# khaliddalkhaldi.net
KiCad netlist of a schematic drawn in EAGLE
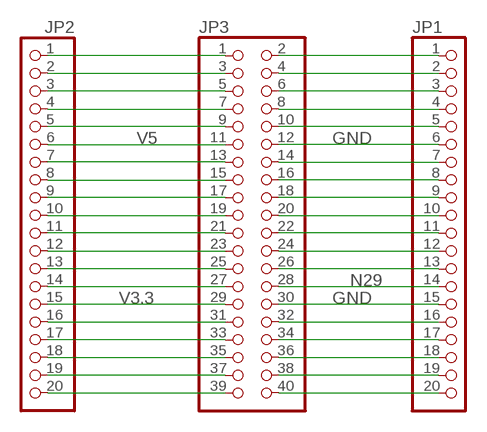
[diagram p0: schematic, sheet 1]

(export (version "E")
  (design (tool "Eeschema 10.0.6"))
  (components
    (comp (ref "JP1")
      (value "PINHD-1X20")
      (footprint "eagle-import:1X20")
      (libsource (lib "eagle-import") (part "PINHD-1X20"))
    )
    (comp (ref "JP2")
      (value "PINHD-1X20")
      (footprint "eagle-import:1X20")
      (libsource (lib "eagle-import") (part "PINHD-1X20"))
    )
    (comp (ref "JP3")
      (value "PINHD-2X20")
      (footprint "eagle-import:2X20")
      (libsource (lib "eagle-import") (part "PINHD-2X20"))
    )
  )
  (nets
    (net (code "1") (name "/GND") (class "Default")
      (node (ref "JP1") (pin "15") (pinfunction "15_15") (pintype "passive"))
      (node (ref "JP1") (pin "6") (pinfunction "6_6") (pintype "passive"))
      (node (ref "JP3") (pin "12") (pinfunction "12_12") (pintype "passive"))
      (node (ref "JP3") (pin "30") (pinfunction "30_30") (pintype "passive"))
    )
    (net (code "2") (name "/N29") (class "Default")
      (node (ref "JP1") (pin "14") (pinfunction "14_14") (pintype "passive"))
      (node (ref "JP3") (pin "28") (pinfunction "28_28") (pintype "passive"))
    )
    (net (code "3") (name "/V3.3") (class "Default")
      (node (ref "JP2") (pin "15") (pinfunction "15_15") (pintype "passive"))
      (node (ref "JP3") (pin "29") (pinfunction "29_29") (pintype "passive"))
    )
    (net (code "4") (name "/V5") (class "Default")
      (node (ref "JP2") (pin "6") (pinfunction "6_6") (pintype "passive"))
      (node (ref "JP3") (pin "11") (pinfunction "11_11") (pintype "passive"))
    )
    (net (code "5") (name "Net-(JP1-Pad1)") (class "Default")
      (node (ref "JP1") (pin "1") (pinfunction "1_1") (pintype "passive"))
      (node (ref "JP3") (pin "2") (pinfunction "2_2") (pintype "passive"))
    )
    (net (code "6") (name "Net-(JP1-Pad2)") (class "Default")
      (node (ref "JP1") (pin "2") (pinfunction "2_2") (pintype "passive"))
      (node (ref "JP3") (pin "4") (pinfunction "4_4") (pintype "passive"))
    )
    (net (code "7") (name "Net-(JP1-Pad3)") (class "Default")
      (node (ref "JP1") (pin "3") (pinfunction "3_3") (pintype "passive"))
      (node (ref "JP3") (pin "6") (pinfunction "6_6") (pintype "passive"))
    )
    (net (code "8") (name "Net-(JP1-Pad4)") (class "Default")
      (node (ref "JP1") (pin "4") (pinfunction "4_4") (pintype "passive"))
      (node (ref "JP3") (pin "8") (pinfunction "8_8") (pintype "passive"))
    )
    (net (code "9") (name "Net-(JP1-Pad5)") (class "Default")
      (node (ref "JP1") (pin "5") (pinfunction "5_5") (pintype "passive"))
      (node (ref "JP3") (pin "10") (pinfunction "10_10") (pintype "passive"))
    )
    (net (code "10") (name "Net-(JP1-Pad7)") (class "Default")
      (node (ref "JP1") (pin "7") (pinfunction "7_7") (pintype "passive"))
      (node (ref "JP3") (pin "14") (pinfunction "14_14") (pintype "passive"))
    )
    (net (code "11") (name "Net-(JP1-Pad8)") (class "Default")
      (node (ref "JP1") (pin "8") (pinfunction "8_8") (pintype "passive"))
      (node (ref "JP3") (pin "16") (pinfunction "16_16") (pintype "passive"))
    )
    (net (code "12") (name "Net-(JP1-Pad9)") (class "Default")
      (node (ref "JP1") (pin "9") (pinfunction "9_9") (pintype "passive"))
      (node (ref "JP3") (pin "18") (pinfunction "18_18") (pintype "passive"))
    )
    (net (code "13") (name "Net-(JP1-Pad10)") (class "Default")
      (node (ref "JP1") (pin "10") (pinfunction "10_10") (pintype "passive"))
      (node (ref "JP3") (pin "20") (pinfunction "20_20") (pintype "passive"))
    )
    (net (code "14") (name "Net-(JP1-Pad11)") (class "Default")
      (node (ref "JP1") (pin "11") (pinfunction "11_11") (pintype "passive"))
      (node (ref "JP3") (pin "22") (pinfunction "22_22") (pintype "passive"))
    )
    (net (code "15") (name "Net-(JP1-Pad12)") (class "Default")
      (node (ref "JP1") (pin "12") (pinfunction "12_12") (pintype "passive"))
      (node (ref "JP3") (pin "24") (pinfunction "24_24") (pintype "passive"))
    )
    (net (code "16") (name "Net-(JP1-Pad13)") (class "Default")
      (node (ref "JP1") (pin "13") (pinfunction "13_13") (pintype "passive"))
      (node (ref "JP3") (pin "26") (pinfunction "26_26") (pintype "passive"))
    )
    (net (code "17") (name "Net-(JP1-Pad16)") (class "Default")
      (node (ref "JP1") (pin "16") (pinfunction "16_16") (pintype "passive"))
      (node (ref "JP3") (pin "32") (pinfunction "32_32") (pintype "passive"))
    )
    (net (code "18") (name "Net-(JP1-Pad17)") (class "Default")
      (node (ref "JP1") (pin "17") (pinfunction "17_17") (pintype "passive"))
      (node (ref "JP3") (pin "34") (pinfunction "34_34") (pintype "passive"))
    )
    (net (code "19") (name "Net-(JP1-Pad18)") (class "Default")
      (node (ref "JP1") (pin "18") (pinfunction "18_18") (pintype "passive"))
      (node (ref "JP3") (pin "36") (pinfunction "36_36") (pintype "passive"))
    )
    (net (code "20") (name "Net-(JP1-Pad19)") (class "Default")
      (node (ref "JP1") (pin "19") (pinfunction "19_19") (pintype "passive"))
      (node (ref "JP3") (pin "38") (pinfunction "38_38") (pintype "passive"))
    )
    (net (code "21") (name "Net-(JP1-Pad20)") (class "Default")
      (node (ref "JP1") (pin "20") (pinfunction "20_20") (pintype "passive"))
      (node (ref "JP3") (pin "40") (pinfunction "40_40") (pintype "passive"))
    )
    (net (code "22") (name "Net-(JP2-Pad1)") (class "Default")
      (node (ref "JP2") (pin "1") (pinfunction "1_1") (pintype "passive"))
      (node (ref "JP3") (pin "1") (pinfunction "1_1") (pintype "passive"))
    )
    (net (code "23") (name "Net-(JP2-Pad2)") (class "Default")
      (node (ref "JP2") (pin "2") (pinfunction "2_2") (pintype "passive"))
      (node (ref "JP3") (pin "3") (pinfunction "3_3") (pintype "passive"))
    )
    (net (code "24") (name "Net-(JP2-Pad3)") (class "Default")
      (node (ref "JP2") (pin "3") (pinfunction "3_3") (pintype "passive"))
      (node (ref "JP3") (pin "5") (pinfunction "5_5") (pintype "passive"))
    )
    (net (code "25") (name "Net-(JP2-Pad4)") (class "Default")
      (node (ref "JP2") (pin "4") (pinfunction "4_4") (pintype "passive"))
      (node (ref "JP3") (pin "7") (pinfunction "7_7") (pintype "passive"))
    )
    (net (code "26") (name "Net-(JP2-Pad5)") (class "Default")
      (node (ref "JP2") (pin "5") (pinfunction "5_5") (pintype "passive"))
      (node (ref "JP3") (pin "9") (pinfunction "9_9") (pintype "passive"))
    )
    (net (code "27") (name "Net-(JP2-Pad7)") (class "Default")
      (node (ref "JP2") (pin "7") (pinfunction "7_7") (pintype "passive"))
      (node (ref "JP3") (pin "13") (pinfunction "13_13") (pintype "passive"))
    )
    (net (code "28") (name "Net-(JP2-Pad8)") (class "Default")
      (node (ref "JP2") (pin "8") (pinfunction "8_8") (pintype "passive"))
      (node (ref "JP3") (pin "15") (pinfunction "15_15") (pintype "passive"))
    )
    (net (code "29") (name "Net-(JP2-Pad9)") (class "Default")
      (node (ref "JP2") (pin "9") (pinfunction "9_9") (pintype "passive"))
      (node (ref "JP3") (pin "17") (pinfunction "17_17") (pintype "passive"))
    )
    (net (code "30") (name "Net-(JP2-Pad10)") (class "Default")
      (node (ref "JP2") (pin "10") (pinfunction "10_10") (pintype "passive"))
      (node (ref "JP3") (pin "19") (pinfunction "19_19") (pintype "passive"))
    )
    (net (code "31") (name "Net-(JP2-Pad11)") (class "Default")
      (node (ref "JP2") (pin "11") (pinfunction "11_11") (pintype "passive"))
      (node (ref "JP3") (pin "21") (pinfunction "21_21") (pintype "passive"))
    )
    (net (code "32") (name "Net-(JP2-Pad12)") (class "Default")
      (node (ref "JP2") (pin "12") (pinfunction "12_12") (pintype "passive"))
      (node (ref "JP3") (pin "23") (pinfunction "23_23") (pintype "passive"))
    )
    (net (code "33") (name "Net-(JP2-Pad13)") (class "Default")
      (node (ref "JP2") (pin "13") (pinfunction "13_13") (pintype "passive"))
      (node (ref "JP3") (pin "25") (pinfunction "25_25") (pintype "passive"))
    )
    (net (code "34") (name "Net-(JP2-Pad14)") (class "Default")
      (node (ref "JP2") (pin "14") (pinfunction "14_14") (pintype "passive"))
      (node (ref "JP3") (pin "27") (pinfunction "27_27") (pintype "passive"))
    )
    (net (code "35") (name "Net-(JP2-Pad16)") (class "Default")
      (node (ref "JP2") (pin "16") (pinfunction "16_16") (pintype "passive"))
      (node (ref "JP3") (pin "31") (pinfunction "31_31") (pintype "passive"))
    )
    (net (code "36") (name "Net-(JP2-Pad17)") (class "Default")
      (node (ref "JP2") (pin "17") (pinfunction "17_17") (pintype "passive"))
      (node (ref "JP3") (pin "33") (pinfunction "33_33") (pintype "passive"))
    )
    (net (code "37") (name "Net-(JP2-Pad18)") (class "Default")
      (node (ref "JP2") (pin "18") (pinfunction "18_18") (pintype "passive"))
      (node (ref "JP3") (pin "35") (pinfunction "35_35") (pintype "passive"))
    )
    (net (code "38") (name "Net-(JP2-Pad19)") (class "Default")
      (node (ref "JP2") (pin "19") (pinfunction "19_19") (pintype "passive"))
      (node (ref "JP3") (pin "37") (pinfunction "37_37") (pintype "passive"))
    )
    (net (code "39") (name "Net-(JP2-Pad20)") (class "Default")
      (node (ref "JP2") (pin "20") (pinfunction "20_20") (pintype "passive"))
      (node (ref "JP3") (pin "39") (pinfunction "39_39") (pintype "passive"))
    )
  )
)
